# HEATER_and_DRIVER.net
KiCad netlist of a schematic drawn in Altium Designer
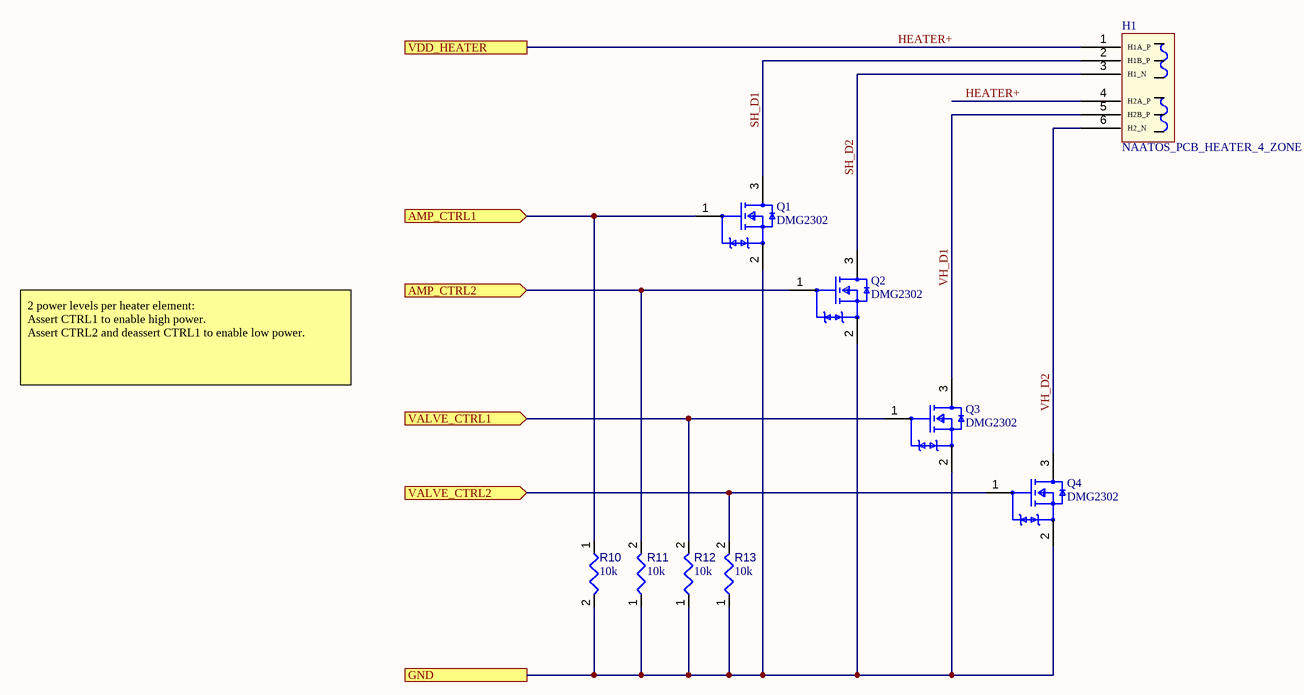
[diagram p0: HEATER and DRIVER.SchDoc]

(export (version "E")
  (design (tool "Eeschema 10.0.6"))
  (components
    (comp (ref "H1")
      (value "NAATOS_PCB_HEATER_4_ZONE")
      (footprint "REV9-1")
      (libsource (lib "Integrated_Library - 21.10.25 - 13.14") (part "CMP-448-000000-8"))
    )
    (comp (ref "Q1")
      (value "DMG2302")
      (footprint "FP-SOT23-MFG")
      (libsource (lib "Global Health Labs, Inc") (part "87c0c04a04979492222792dd46c39c9"))
    )
    (comp (ref "Q2")
      (value "DMG2302")
      (footprint "FP-SOT23-MFG")
      (libsource (lib "Global Health Labs, Inc") (part "87c0c04a04979492222792dd46c39c9"))
    )
    (comp (ref "Q3")
      (value "DMG2302")
      (footprint "FP-SOT23-MFG")
      (libsource (lib "Global Health Labs, Inc") (part "87c0c04a04979492222792dd46c39c9"))
    )
    (comp (ref "Q4")
      (value "DMG2302")
      (footprint "FP-SOT23-MFG")
      (libsource (lib "Global Health Labs, Inc") (part "87c0c04a04979492222792dd46c39c9"))
    )
    (comp (ref "R10")
      (value "10k")
      (footprint "RESC0402(1005)_L")
      (description "Chip Resistor, 10 kOhms, +/-1 %, 63 mW, -55 to 125 degC, 0402")
      (fields (field (name "POWER") "63mW") (field (name "TOLERANCE") "1%"))
      (libsource (lib "Global Health Labs, Inc") (part "RES-2"))
    )
    (comp (ref "R11")
      (value "10k")
      (footprint "RESC0402(1005)_L")
      (description "Chip Resistor, 10 kOhms, +/-1 %, 63 mW, -55 to 125 degC, 0402")
      (fields (field (name "POWER") "63mW") (field (name "TOLERANCE") "1%"))
      (libsource (lib "Global Health Labs, Inc") (part "RES-2"))
    )
    (comp (ref "R12")
      (value "10k")
      (footprint "RESC0402(1005)_L")
      (description "Chip Resistor, 10 kOhms, +/-1 %, 63 mW, -55 to 125 degC, 0402")
      (fields (field (name "POWER") "63mW") (field (name "TOLERANCE") "1%"))
      (libsource (lib "Global Health Labs, Inc") (part "RES-2"))
    )
    (comp (ref "R13")
      (value "10k")
      (footprint "RESC0402(1005)_L")
      (description "Chip Resistor, 10 kOhms, +/-1 %, 63 mW, -55 to 125 degC, 0402")
      (fields (field (name "POWER") "63mW") (field (name "TOLERANCE") "1%"))
      (libsource (lib "Global Health Labs, Inc") (part "RES-2"))
    )
  )
  (nets
    (net (code "1") (name "/AMP_CTRL1") (class "Default")
      (node (ref "Q1") (pin "1") (pinfunction "G_1") (pintype "passive"))
      (node (ref "R10") (pin "1") (pinfunction "1_1") (pintype "passive"))
    )
    (net (code "2") (name "/AMP_CTRL2") (class "Default")
      (node (ref "Q2") (pin "1") (pinfunction "G_1") (pintype "passive"))
      (node (ref "R11") (pin "2") (pinfunction "2_2") (pintype "passive"))
    )
    (net (code "3") (name "/GND") (class "Default")
      (node (ref "Q1") (pin "2") (pinfunction "S_2") (pintype "passive"))
      (node (ref "Q2") (pin "2") (pinfunction "S_2") (pintype "passive"))
      (node (ref "Q3") (pin "2") (pinfunction "S_2") (pintype "passive"))
      (node (ref "Q4") (pin "2") (pinfunction "S_2") (pintype "passive"))
      (node (ref "R10") (pin "2") (pinfunction "2_2") (pintype "passive"))
      (node (ref "R11") (pin "1") (pinfunction "1_1") (pintype "passive"))
      (node (ref "R12") (pin "1") (pinfunction "1_1") (pintype "passive"))
      (node (ref "R13") (pin "1") (pinfunction "1_1") (pintype "passive"))
    )
    (net (code "4") (name "/HEATER+") (class "Default")
      (node (ref "H1") (pin "1") (pinfunction "H1A_P_1") (pintype "passive"))
      (node (ref "H1") (pin "4") (pinfunction "H2A_P_4") (pintype "passive"))
    )
    (net (code "5") (name "/SH_D1") (class "Default")
      (node (ref "H1") (pin "2") (pinfunction "H1B_P_2") (pintype "passive"))
      (node (ref "Q1") (pin "3") (pinfunction "D_3") (pintype "passive"))
    )
    (net (code "6") (name "/SH_D2") (class "Default")
      (node (ref "H1") (pin "3") (pinfunction "H1_N_3") (pintype "passive"))
      (node (ref "Q2") (pin "3") (pinfunction "D_3") (pintype "passive"))
    )
    (net (code "7") (name "/VALVE_CTRL1") (class "Default")
      (node (ref "Q3") (pin "1") (pinfunction "G_1") (pintype "passive"))
      (node (ref "R12") (pin "2") (pinfunction "2_2") (pintype "passive"))
    )
    (net (code "8") (name "/VALVE_CTRL2") (class "Default")
      (node (ref "Q4") (pin "1") (pinfunction "G_1") (pintype "passive"))
      (node (ref "R13") (pin "2") (pinfunction "2_2") (pintype "passive"))
    )
    (net (code "9") (name "/VH_D1") (class "Default")
      (node (ref "H1") (pin "5") (pinfunction "H2B_P_5") (pintype "passive"))
      (node (ref "Q3") (pin "3") (pinfunction "D_3") (pintype "passive"))
    )
    (net (code "10") (name "/VH_D2") (class "Default")
      (node (ref "H1") (pin "6") (pinfunction "H2_N_6") (pintype "passive"))
      (node (ref "Q4") (pin "3") (pinfunction "D_3") (pintype "passive"))
    )
  )
)
